# Power.net
KiCad netlist of a schematic drawn in Altium Designer
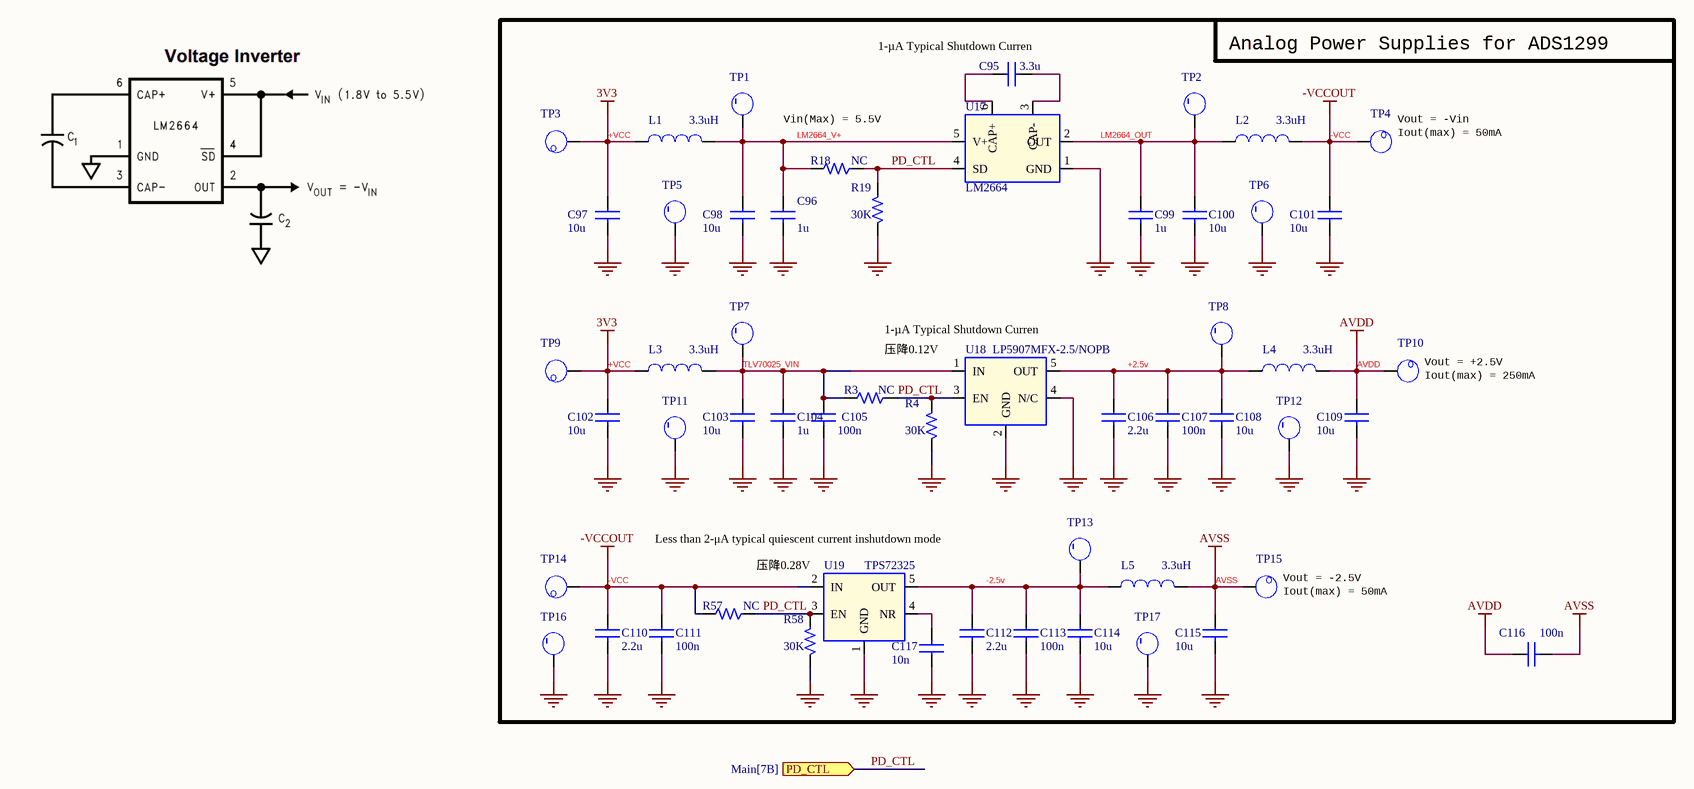
[diagram p0: Power.SchDoc]

(export (version "E")
  (design (tool "Eeschema 10.0.6"))
  (components
    (comp (ref "C95")
      (value "3.3u")
      (footprint "0402_C")
      (description "CAP CER 3.3UF 10V X5R 0805")
      (fields
        (field (name "DISTRIBUTOR PART NUMBER") "C162416")
        (field (name "PART NUMBER") "GRM21BR61A335KA73L")
      )
      (libsource (lib "*") (part "CAP0402"))
    )
    (comp (ref "C96")
      (value "1u")
      (footprint "0402_C")
      (description "CAP CER 1UF 25V X5R 0603")
      (fields
        (field (name "DISTRIBUTOR PART NUMBER") "C77046")
        (field (name "PART NUMBER") "GRM188R61E105KA12D")
      )
      (libsource (lib "*") (part "CAP0402"))
    )
    (comp (ref "C97")
      (value "10u")
      (footprint "0402_C")
      (description "CAP CER 10UF 10V X5R 0603")
      (fields
        (field (name "DISTRIBUTOR PART NUMBER") "C19702")
        (field (name "PART NUMBER") "CL10A106KP8NNNC")
      )
      (libsource (lib "*") (part "CAP0402"))
    )
    (comp (ref "C98")
      (value "10u")
      (footprint "0402_C")
      (description "CAP CER 10UF 10V X5R 0603")
      (fields
        (field (name "DISTRIBUTOR PART NUMBER") "C19702")
        (field (name "PART NUMBER") "CL10A106KP8NNNC")
      )
      (libsource (lib "*") (part "CAP0402"))
    )
    (comp (ref "C99")
      (value "1u")
      (footprint "0402_C")
      (description "CAP CER 1UF 25V X5R 0603")
      (fields
        (field (name "DISTRIBUTOR PART NUMBER") "C77046")
        (field (name "PART NUMBER") "GRM188R61E105KA12D")
      )
      (libsource (lib "*") (part "CAP0402"))
    )
    (comp (ref "C100")
      (value "10u")
      (footprint "0402_C")
      (description "CAP CER 10UF 10V X5R 0603")
      (fields
        (field (name "DISTRIBUTOR PART NUMBER") "C19702")
        (field (name "PART NUMBER") "CL10A106KP8NNNC")
      )
      (libsource (lib "*") (part "CAP0402"))
    )
    (comp (ref "C101")
      (value "10u")
      (footprint "0402_C")
      (description "CAP CER 10UF 10V X5R 0603")
      (fields
        (field (name "DISTRIBUTOR PART NUMBER") "C19702")
        (field (name "PART NUMBER") "CL10A106KP8NNNC")
      )
      (libsource (lib "*") (part "CAP0402"))
    )
    (comp (ref "C102")
      (value "10u")
      (footprint "0402_C")
      (description "CAP CER 10UF 10V X5R 0603")
      (fields
        (field (name "DISTRIBUTOR PART NUMBER") "C19702")
        (field (name "PART NUMBER") "CL10A106KP8NNNC")
      )
      (libsource (lib "*") (part "CAP0402"))
    )
    (comp (ref "C103")
      (value "10u")
      (footprint "0402_C")
      (description "CAP CER 10UF 10V X5R 0603")
      (fields
        (field (name "DISTRIBUTOR PART NUMBER") "C19702")
        (field (name "PART NUMBER") "CL10A106KP8NNNC")
      )
      (libsource (lib "*") (part "CAP0402"))
    )
    (comp (ref "C104")
      (value "1u")
      (footprint "0402_C")
      (description "CAP CER 1UF 25V X5R 0603")
      (fields
        (field (name "DISTRIBUTOR PART NUMBER") "C77046")
        (field (name "PART NUMBER") "GRM188R61E105KA12D")
      )
      (libsource (lib "*") (part "CAP0402"))
    )
    (comp (ref "C105")
      (value "100n")
      (footprint "0402_C")
      (description "CAP CER 0.1UF 25V X7R 0402")
      (fields
        (field (name "DISTRIBUTOR PART NUMBER") "C105883")
        (field (name "PART NUMBER") "CC0402KRX7R8BB104")
      )
      (libsource (lib "*") (part "CAP0402"))
    )
    (comp (ref "C106")
      (value "2.2u")
      (footprint "0402_C")
      (description "CAP CER 2.2UF 25V X5R 0603")
      (fields
        (field (name "DISTRIBUTOR PART NUMBER") "C541409")
        (field (name "PART NUMBER") "CC0603KRX5R8BB225")
      )
      (libsource (lib "*") (part "CAP0402"))
    )
    (comp (ref "C107")
      (value "100n")
      (footprint "0402_C")
      (description "CAP CER 0.1UF 25V X7R 0402")
      (fields
        (field (name "DISTRIBUTOR PART NUMBER") "C105883")
        (field (name "PART NUMBER") "CC0402KRX7R8BB104")
      )
      (libsource (lib "*") (part "CAP0402"))
    )
    (comp (ref "C108")
      (value "10u")
      (footprint "0402_C")
      (description "CAP CER 10UF 10V X5R 0603")
      (fields
        (field (name "DISTRIBUTOR PART NUMBER") "C19702")
        (field (name "PART NUMBER") "CL10A106KP8NNNC")
      )
      (libsource (lib "*") (part "CAP0402"))
    )
    (comp (ref "C109")
      (value "10u")
      (footprint "0402_C")
      (description "CAP CER 10UF 10V X5R 0603")
      (fields
        (field (name "DISTRIBUTOR PART NUMBER") "C19702")
        (field (name "PART NUMBER") "CL10A106KP8NNNC")
      )
      (libsource (lib "*") (part "CAP0402"))
    )
    (comp (ref "C110")
      (value "2.2u")
      (footprint "0402_C")
      (description "CAP CER 2.2UF 25V X5R 0603")
      (fields
        (field (name "DISTRIBUTOR PART NUMBER") "C541409")
        (field (name "PART NUMBER") "CC0603KRX5R8BB225")
      )
      (libsource (lib "*") (part "CAP0402"))
    )
    (comp (ref "C111")
      (value "100n")
      (footprint "0402_C")
      (description "CAP CER 0.1UF 25V X7R 0402")
      (fields
        (field (name "DISTRIBUTOR PART NUMBER") "C105883")
        (field (name "PART NUMBER") "CC0402KRX7R8BB104")
      )
      (libsource (lib "*") (part "CAP0402"))
    )
    (comp (ref "C112")
      (value "2.2u")
      (footprint "0402_C")
      (description "CAP CER 2.2UF 25V X5R 0603")
      (fields
        (field (name "DISTRIBUTOR PART NUMBER") "C541409")
        (field (name "PART NUMBER") "CC0603KRX5R8BB225")
      )
      (libsource (lib "*") (part "CAP0402"))
    )
    (comp (ref "C113")
      (value "100n")
      (footprint "0402_C")
      (description "CAP CER 0.1UF 25V X7R 0402")
      (fields
        (field (name "DISTRIBUTOR PART NUMBER") "C105883")
        (field (name "PART NUMBER") "CC0402KRX7R8BB104")
      )
      (libsource (lib "*") (part "CAP0402"))
    )
    (comp (ref "C114")
      (value "10u")
      (footprint "0402_C")
      (description "CAP CER 10UF 10V X5R 0603")
      (fields
        (field (name "DISTRIBUTOR PART NUMBER") "C19702")
        (field (name "PART NUMBER") "CL10A106KP8NNNC")
      )
      (libsource (lib "*") (part "CAP0402"))
    )
    (comp (ref "C115")
      (value "10u")
      (footprint "0402_C")
      (description "CAP CER 10UF 10V X5R 0603")
      (fields
        (field (name "DISTRIBUTOR PART NUMBER") "C19702")
        (field (name "PART NUMBER") "CL10A106KP8NNNC")
      )
      (libsource (lib "*") (part "CAP0402"))
    )
    (comp (ref "C116")
      (value "100n")
      (footprint "0201_C")
      (description "CAP CER 0.1UF 25V X7R 0402")
      (fields
        (field (name "DISTRIBUTOR PART NUMBER") "C105883")
        (field (name "PART NUMBER") "CC0402KRX7R8BB104")
      )
      (libsource (lib "*") (part "CAP0402"))
    )
    (comp (ref "C117")
      (value "10n")
      (footprint "0402_C")
      (description "CAP CER 10000PF 25V X7R 0402")
      (fields
        (field (name "DISTRIBUTOR PART NUMBER") "C327025")
        (field (name "PART NUMBER") "CC0402KRX7R8BB103")
      )
      (libsource (lib "*") (part "CAP0402"))
    )
    (comp (ref "L1")
      (value "3.3uH")
      (footprint "0805_L")
      (description "FIXED IND 3.3UH 500MA 260 MOHM")
      (fields
        (field (name "PART NUMBER") "KLZ2012MHR3R3HTD25")
        (field (name "MANUFACTURER") "TDK Corporation")
      )
      (libsource (lib "*") (part "INDUCTOR"))
    )
    (comp (ref "L2")
      (value "3.3uH")
      (footprint "0805_L")
      (description "FIXED IND 3.3UH 500MA 260 MOHM")
      (fields
        (field (name "DISTRIBUTOR PART NUMBER") "C404386")
        (field (name "MANUFACTURER") "TDK Corporation")
      )
      (libsource (lib "*") (part "INDUCTOR"))
    )
    (comp (ref "L3")
      (value "3.3uH")
      (footprint "0805_L")
      (description "FIXED IND 3.3UH 500MA 260 MOHM")
      (fields
        (field (name "DISTRIBUTOR PART NUMBER") "C404386")
        (field (name "MANUFACTURER") "TDK Corporation")
      )
      (libsource (lib "*") (part "INDUCTOR"))
    )
    (comp (ref "L4")
      (value "3.3uH")
      (footprint "0805_L")
      (description "FIXED IND 3.3UH 500MA 260 MOHM")
      (fields
        (field (name "DISTRIBUTOR PART NUMBER") "C404386")
        (field (name "MANUFACTURER") "TDK Corporation")
      )
      (libsource (lib "*") (part "INDUCTOR"))
    )
    (comp (ref "L5")
      (value "3.3uH")
      (footprint "0805_L")
      (description "FIXED IND 3.3UH 500MA 260 MOHM")
      (fields
        (field (name "PART NUMBER") "KLZ2012MHR3R3HTD25")
        (field (name "MANUFACTURER") "TDK Corporation")
      )
      (libsource (lib "*") (part "INDUCTOR"))
    )
    (comp (ref "R3")
      (value "NC")
      (footprint "0402_R")
      (description "RES SMD 0 OHM JUMPER 1/16W 0402")
      (fields
        (field (name "DISTRIBUTOR PART NUMBER") "C106231")
        (field (name "PART NUMBER") "RC0402FR-070RL")
      )
      (libsource (lib "*") (part "RES"))
    )
    (comp (ref "R4") (value "30K") (footprint "0402_R") (libsource (lib "*") (part "RES")))
    (comp (ref "R18")
      (value "NC")
      (footprint "0402_R")
      (description "RES SMD 0 OHM JUMPER 1/16W 0402")
      (fields
        (field (name "DISTRIBUTOR PART NUMBER") "C106231")
        (field (name "PART NUMBER") "RC0402FR-070RL")
      )
      (libsource (lib "*") (part "RES"))
    )
    (comp (ref "R19") (value "30K") (footprint "0402_R") (libsource (lib "*") (part "RES")))
    (comp (ref "R57")
      (value "NC")
      (footprint "0402_R")
      (description "RES SMD 0 OHM JUMPER 1/16W 0402")
      (fields
        (field (name "DISTRIBUTOR PART NUMBER") "C106231")
        (field (name "PART NUMBER") "RC0402FR-070RL")
      )
      (libsource (lib "*") (part "RES"))
    )
    (comp (ref "R58") (value "30K") (footprint "0402_R") (libsource (lib "*") (part "RES")))
    (comp (ref "TP1") (value "SMD_TP_C35") (footprint "TEST_Point") (libsource (lib "*") (part "CON1_0")))
    (comp (ref "TP2") (value "SMD_TP_C35") (footprint "TEST_Point") (libsource (lib "*") (part "CON1_0")))
    (comp (ref "TP3") (value "SMD_TP_C35") (footprint "TEST_Point") (libsource (lib "*") (part "CON1_0")))
    (comp (ref "TP4") (value "SMD_TP_C35") (footprint "TEST_Point") (libsource (lib "*") (part "CON1_0")))
    (comp (ref "TP5") (value "SMD_TP_C35") (footprint "TEST_Point") (libsource (lib "*") (part "CON1_0")))
    (comp (ref "TP6") (value "SMD_TP_C35") (footprint "TEST_Point") (libsource (lib "*") (part "CON1_0")))
    (comp (ref "TP7") (value "SMD_TP_C35") (footprint "TEST_Point") (libsource (lib "*") (part "CON1_0")))
    (comp (ref "TP8") (value "SMD_TP_C35") (footprint "TEST_Point") (libsource (lib "*") (part "CON1_0")))
    (comp (ref "TP9") (value "SMD_TP_C35") (footprint "TEST_Point") (libsource (lib "*") (part "CON1_0")))
    (comp (ref "TP10") (value "SMD_TP_C35") (footprint "TEST_Point") (libsource (lib "*") (part "CON1_0")))
    (comp (ref "TP11") (value "SMD_TP_C35") (footprint "TEST_Point") (libsource (lib "*") (part "CON1_0")))
    (comp (ref "TP12") (value "SMD_TP_C35") (footprint "TEST_Point") (libsource (lib "*") (part "CON1_0")))
    (comp (ref "TP13") (value "SMD_TP_C35") (footprint "TEST_Point") (libsource (lib "*") (part "CON1_0")))
    (comp (ref "TP14") (value "SMD_TP_C35") (footprint "TEST_Point") (libsource (lib "*") (part "CON1_0")))
    (comp (ref "TP15") (value "SMD_TP_C35") (footprint "TEST_Point") (libsource (lib "*") (part "CON1_0")))
    (comp (ref "TP16") (value "SMD_TP_C35") (footprint "TEST_Point") (libsource (lib "*") (part "CON1_0")))
    (comp (ref "TP17") (value "SMD_TP_C35") (footprint "TEST_Point") (libsource (lib "*") (part "CON1_0")))
    (comp (ref "U17")
      (value "LM2664")
      (footprint "SOT-23-6")
      (description "IC REG CHARG PUMP INV 40MA SOT23")
      (fields
        (field (name "DISTRIBUTOR PART NUMBER") "C108573")
        (field (name "MANUFACTURER PART NUMBER") "LM2664M6X/NOPB")
      )
      (libsource (lib "*") (part "LM2664"))
    )
    (comp (ref "U18")
      (value "LP5907MFX-2.5/NOPB")
      (footprint "SOT-23_5")
      (description "IC REG LINEAR 2.5V 250MA SOT23-5")
      (fields
        (field (name "MANUFACTURER") "Texas Instruments")
        (field (name "DISTRIBUTOR PART NUMBER") "C165132")
      )
      (libsource (lib "*") (part "LP5907"))
    )
    (comp (ref "U19")
      (value "TPS72325")
      (footprint "SOT-23_5")
      (description "IC REG LIN -2.5V 200MA SOT23-5")
      (fields
        (field (name "MANUFACTURER PART NUMBER") "TPS72325DBVR")
        (field (name "MANUFACTURER") "Texas Instruments")
      )
      (libsource (lib "*") (part "TPS72325"))
    )
  )
  (nets
    (net (code "1") (name "-VCCOUT") (class "Default")
      (node (ref "C101") (pin "1") (pinfunction "1_1") (pintype "passive"))
      (node (ref "C110") (pin "1") (pinfunction "1_1") (pintype "passive"))
      (node (ref "C111") (pin "1") (pinfunction "1_1") (pintype "passive"))
      (node (ref "L2") (pin "2") (pinfunction "2_2") (pintype "passive"))
      (node (ref "R57") (pin "2") (pinfunction "2_2") (pintype "passive"))
      (node (ref "TP14") (pin "1") (pinfunction "1_1") (pintype "passive"))
      (node (ref "TP4") (pin "1") (pinfunction "1_1") (pintype "passive"))
      (node (ref "U19") (pin "2") (pinfunction "IN_2") (pintype "passive"))
    )
    (net (code "2") (name "/+2.5v") (class "Default")
      (node (ref "C106") (pin "1") (pinfunction "1_1") (pintype "passive"))
      (node (ref "C107") (pin "1") (pinfunction "1_1") (pintype "passive"))
      (node (ref "C108") (pin "1") (pinfunction "1_1") (pintype "passive"))
      (node (ref "L4") (pin "1") (pinfunction "1_1") (pintype "passive"))
      (node (ref "TP8") (pin "1") (pinfunction "1_1") (pintype "passive"))
      (node (ref "U18") (pin "5") (pinfunction "OUT_5") (pintype "passive"))
    )
    (net (code "3") (name "/-2.5v") (class "Default")
      (node (ref "C112") (pin "1") (pinfunction "1_1") (pintype "passive"))
      (node (ref "C113") (pin "1") (pinfunction "1_1") (pintype "passive"))
      (node (ref "C114") (pin "1") (pinfunction "1_1") (pintype "passive"))
      (node (ref "L5") (pin "1") (pinfunction "1_1") (pintype "passive"))
      (node (ref "TP13") (pin "1") (pinfunction "1_1") (pintype "passive"))
      (node (ref "U19") (pin "5") (pinfunction "OUT_5") (pintype "passive"))
    )
    (net (code "4") (name "/LM2664_OUT") (class "Default")
      (node (ref "C100") (pin "1") (pinfunction "1_1") (pintype "passive"))
      (node (ref "C99") (pin "1") (pinfunction "1_1") (pintype "passive"))
      (node (ref "L2") (pin "1") (pinfunction "1_1") (pintype "passive"))
      (node (ref "TP2") (pin "1") (pinfunction "1_1") (pintype "passive"))
      (node (ref "U17") (pin "2") (pinfunction "OUT_2") (pintype "passive"))
    )
    (net (code "5") (name "/LM2664_V+") (class "Default")
      (node (ref "C96") (pin "1") (pinfunction "1_1") (pintype "passive"))
      (node (ref "C98") (pin "1") (pinfunction "1_1") (pintype "passive"))
      (node (ref "L1") (pin "2") (pinfunction "2_2") (pintype "passive"))
      (node (ref "R18") (pin "2") (pinfunction "2_2") (pintype "passive"))
      (node (ref "TP1") (pin "1") (pinfunction "1_1") (pintype "passive"))
      (node (ref "U17") (pin "5") (pinfunction "V+_5") (pintype "passive"))
    )
    (net (code "6") (name "/PD_CTL") (class "Default")
      (node (ref "R18") (pin "1") (pinfunction "1_1") (pintype "passive"))
      (node (ref "R19") (pin "1") (pinfunction "1_1") (pintype "passive"))
      (node (ref "R3") (pin "1") (pinfunction "1_1") (pintype "passive"))
      (node (ref "R4") (pin "1") (pinfunction "1_1") (pintype "passive"))
      (node (ref "R57") (pin "1") (pinfunction "1_1") (pintype "passive"))
      (node (ref "R58") (pin "1") (pinfunction "1_1") (pintype "passive"))
      (node (ref "U17") (pin "4") (pinfunction "SD_4") (pintype "passive"))
      (node (ref "U18") (pin "3") (pinfunction "EN_3") (pintype "passive"))
      (node (ref "U19") (pin "3") (pinfunction "EN_3") (pintype "passive"))
    )
    (net (code "7") (name "/TLV70025_VIN") (class "Default")
      (node (ref "C103") (pin "1") (pinfunction "1_1") (pintype "passive"))
      (node (ref "C104") (pin "1") (pinfunction "1_1") (pintype "passive"))
      (node (ref "C105") (pin "1") (pinfunction "1_1") (pintype "passive"))
      (node (ref "L3") (pin "2") (pinfunction "2_2") (pintype "passive"))
      (node (ref "R3") (pin "2") (pinfunction "2_2") (pintype "passive"))
      (node (ref "TP7") (pin "1") (pinfunction "1_1") (pintype "passive"))
      (node (ref "U18") (pin "1") (pinfunction "IN_1") (pintype "passive"))
    )
    (net (code "8") (name "3V3") (class "Default")
      (node (ref "C102") (pin "1") (pinfunction "1_1") (pintype "passive"))
      (node (ref "C97") (pin "1") (pinfunction "1_1") (pintype "passive"))
      (node (ref "L1") (pin "1") (pinfunction "1_1") (pintype "passive"))
      (node (ref "L3") (pin "1") (pinfunction "1_1") (pintype "passive"))
      (node (ref "TP3") (pin "1") (pinfunction "1_1") (pintype "passive"))
      (node (ref "TP9") (pin "1") (pinfunction "1_1") (pintype "passive"))
    )
    (net (code "9") (name "AVDD") (class "Default")
      (node (ref "C109") (pin "1") (pinfunction "1_1") (pintype "passive"))
      (node (ref "C116") (pin "1") (pinfunction "1_1") (pintype "passive"))
      (node (ref "L4") (pin "2") (pinfunction "2_2") (pintype "passive"))
      (node (ref "TP10") (pin "1") (pinfunction "1_1") (pintype "passive"))
    )
    (net (code "10") (name "AVSS") (class "Default")
      (node (ref "C115") (pin "1") (pinfunction "1_1") (pintype "passive"))
      (node (ref "C116") (pin "2") (pinfunction "2_2") (pintype "passive"))
      (node (ref "L5") (pin "2") (pinfunction "2_2") (pintype "passive"))
      (node (ref "TP15") (pin "1") (pinfunction "1_1") (pintype "passive"))
    )
    (net (code "11") (name "GND") (class "Default")
      (node (ref "C100") (pin "2") (pinfunction "2_2") (pintype "passive"))
      (node (ref "C101") (pin "2") (pinfunction "2_2") (pintype "passive"))
      (node (ref "C102") (pin "2") (pinfunction "2_2") (pintype "passive"))
      (node (ref "C103") (pin "2") (pinfunction "2_2") (pintype "passive"))
      (node (ref "C104") (pin "2") (pinfunction "2_2") (pintype "passive"))
      (node (ref "C105") (pin "2") (pinfunction "2_2") (pintype "passive"))
      (node (ref "C106") (pin "2") (pinfunction "2_2") (pintype "passive"))
      (node (ref "C107") (pin "2") (pinfunction "2_2") (pintype "passive"))
      (node (ref "C108") (pin "2") (pinfunction "2_2") (pintype "passive"))
      (node (ref "C109") (pin "2") (pinfunction "2_2") (pintype "passive"))
      (node (ref "C110") (pin "2") (pinfunction "2_2") (pintype "passive"))
      (node (ref "C111") (pin "2") (pinfunction "2_2") (pintype "passive"))
      (node (ref "C112") (pin "2") (pinfunction "2_2") (pintype "passive"))
      (node (ref "C113") (pin "2") (pinfunction "2_2") (pintype "passive"))
      (node (ref "C114") (pin "2") (pinfunction "2_2") (pintype "passive"))
      (node (ref "C115") (pin "2") (pinfunction "2_2") (pintype "passive"))
      (node (ref "C117") (pin "1") (pinfunction "1_1") (pintype "passive"))
      (node (ref "C96") (pin "2") (pinfunction "2_2") (pintype "passive"))
      (node (ref "C97") (pin "2") (pinfunction "2_2") (pintype "passive"))
      (node (ref "C98") (pin "2") (pinfunction "2_2") (pintype "passive"))
      (node (ref "C99") (pin "2") (pinfunction "2_2") (pintype "passive"))
      (node (ref "R19") (pin "2") (pinfunction "2_2") (pintype "passive"))
      (node (ref "R4") (pin "2") (pinfunction "2_2") (pintype "passive"))
      (node (ref "R58") (pin "2") (pinfunction "2_2") (pintype "passive"))
      (node (ref "TP11") (pin "1") (pinfunction "1_1") (pintype "passive"))
      (node (ref "TP12") (pin "1") (pinfunction "1_1") (pintype "passive"))
      (node (ref "TP16") (pin "1") (pinfunction "1_1") (pintype "passive"))
      (node (ref "TP17") (pin "1") (pinfunction "1_1") (pintype "passive"))
      (node (ref "TP5") (pin "1") (pinfunction "1_1") (pintype "passive"))
      (node (ref "TP6") (pin "1") (pinfunction "1_1") (pintype "passive"))
      (node (ref "U17") (pin "1") (pinfunction "GND_1") (pintype "passive"))
      (node (ref "U18") (pin "2") (pinfunction "GND_2") (pintype "passive"))
      (node (ref "U18") (pin "4") (pinfunction "N/C_4") (pintype "passive"))
      (node (ref "U19") (pin "1") (pinfunction "GND_1") (pintype "passive"))
    )
    (net (code "12") (name "Net-(U17-CAP+)") (class "Default")
      (node (ref "C95") (pin "1") (pinfunction "1_1") (pintype "passive"))
      (node (ref "U17") (pin "6") (pinfunction "CAP+_6") (pintype "passive"))
    )
    (net (code "13") (name "Net-(U17-CAP-)") (class "Default")
      (node (ref "C95") (pin "2") (pinfunction "2_2") (pintype "passive"))
      (node (ref "U17") (pin "3") (pinfunction "CAP-_3") (pintype "passive"))
    )
    (net (code "14") (name "Net-(U19-NR)") (class "Default")
      (node (ref "C117") (pin "2") (pinfunction "2_2") (pintype "passive"))
      (node (ref "U19") (pin "4") (pinfunction "NR_4") (pintype "passive"))
    )
  )
)
